# AnalogConnectors.net
KiCad netlist of a schematic drawn in Altium Designer
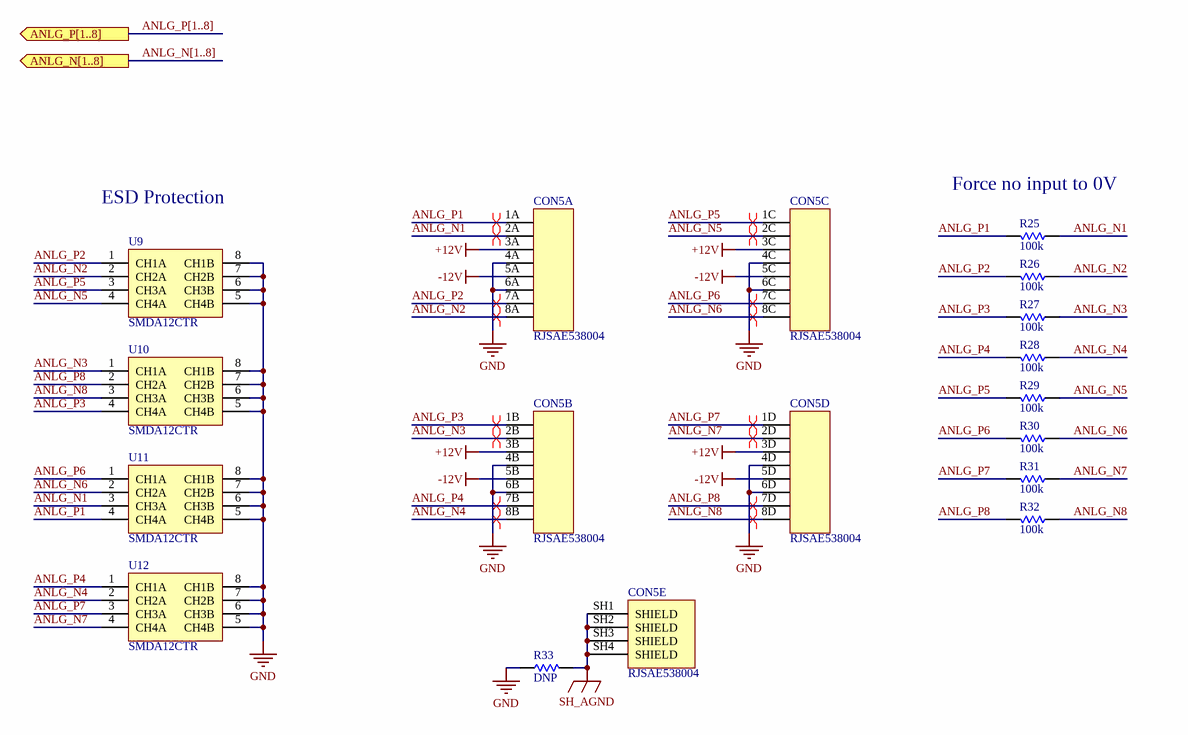
[diagram p0: AnalogConnectors.SchDoc]

(export (version "E")
  (design (tool "Eeschema 10.0.6"))
  (components
    (comp (ref "CON5")
      (value "RJSAE538004")
      (footprint "AMDC:RJSAE538004")
      (description "CONN MOD JACK 8P8C R/A SHIELDED")
      (libsource (lib "AMDC") (part "RJSAE538004"))
    )
    (comp (ref "R25")
      (value "100k")
      (footprint "AMDC:0603-RES")
      (description "Resistor")
      (libsource (lib "AMDC") (part "Resistor"))
    )
    (comp (ref "R26")
      (value "100k")
      (footprint "AMDC:0603-RES")
      (description "Resistor")
      (libsource (lib "AMDC") (part "Resistor"))
    )
    (comp (ref "R27")
      (value "100k")
      (footprint "AMDC:0603-RES")
      (description "Resistor")
      (libsource (lib "AMDC") (part "Resistor"))
    )
    (comp (ref "R28")
      (value "100k")
      (footprint "AMDC:0603-RES")
      (description "Resistor")
      (libsource (lib "AMDC") (part "Resistor"))
    )
    (comp (ref "R29")
      (value "100k")
      (footprint "AMDC:0603-RES")
      (description "Resistor")
      (libsource (lib "AMDC") (part "Resistor"))
    )
    (comp (ref "R30")
      (value "100k")
      (footprint "AMDC:0603-RES")
      (description "Resistor")
      (libsource (lib "AMDC") (part "Resistor"))
    )
    (comp (ref "R31")
      (value "100k")
      (footprint "AMDC:0603-RES")
      (description "Resistor")
      (libsource (lib "AMDC") (part "Resistor"))
    )
    (comp (ref "R32")
      (value "100k")
      (footprint "AMDC:0603-RES")
      (description "Resistor")
      (libsource (lib "AMDC") (part "Resistor"))
    )
    (comp (ref "R33")
      (value "DNP")
      (footprint "AMDC:0603-RES")
      (description "Resistor")
      (libsource (lib "AMDC") (part "Resistor"))
    )
    (comp (ref "U9")
      (value "SMDA12CTR")
      (footprint "AMDC:SOIC127P600X175-8N")
      (description "TVS DIODE 12V 19V 8SO")
      (libsource (lib "AMDC") (part "SMDA12CTR"))
    )
    (comp (ref "U10")
      (value "SMDA12CTR")
      (footprint "AMDC:SOIC127P600X175-8N")
      (description "TVS DIODE 12V 19V 8SO")
      (libsource (lib "AMDC") (part "SMDA12CTR"))
    )
    (comp (ref "U11")
      (value "SMDA12CTR")
      (footprint "AMDC:SOIC127P600X175-8N")
      (description "TVS DIODE 12V 19V 8SO")
      (libsource (lib "AMDC") (part "SMDA12CTR"))
    )
    (comp (ref "U12")
      (value "SMDA12CTR")
      (footprint "AMDC:SOIC127P600X175-8N")
      (description "TVS DIODE 12V 19V 8SO")
      (libsource (lib "AMDC") (part "SMDA12CTR"))
    )
  )
  (nets
    (net (code "1") (name "+12V") (class "Default")
      (node (ref "CON5") (pin "3A") (pinfunction "79_3A") (pintype "passive"))
      (node (ref "CON5") (pin "3B") (pinfunction "79_3B") (pintype "passive"))
      (node (ref "CON5") (pin "3C") (pinfunction "79_3C") (pintype "passive"))
      (node (ref "CON5") (pin "3D") (pinfunction "79_3D") (pintype "passive"))
    )
    (net (code "2") (name "-12V") (class "Default")
      (node (ref "CON5") (pin "5A") (pinfunction "79_5A") (pintype "passive"))
      (node (ref "CON5") (pin "5B") (pinfunction "79_5B") (pintype "passive"))
      (node (ref "CON5") (pin "5C") (pinfunction "79_5C") (pintype "passive"))
      (node (ref "CON5") (pin "5D") (pinfunction "79_5D") (pintype "passive"))
    )
    (net (code "3") (name "/ANLG_N1") (class "Default")
      (node (ref "CON5") (pin "2A") (pinfunction "79_2A") (pintype "passive"))
      (node (ref "R25") (pin "1") (pinfunction "1_1") (pintype "passive"))
      (node (ref "U11") (pin "3") (pinfunction "CH3A_3") (pintype "passive"))
    )
    (net (code "4") (name "/ANLG_N2") (class "Default")
      (node (ref "CON5") (pin "8A") (pinfunction "79_8A") (pintype "passive"))
      (node (ref "R26") (pin "1") (pinfunction "1_1") (pintype "passive"))
      (node (ref "U9") (pin "2") (pinfunction "CH2A_2") (pintype "passive"))
    )
    (net (code "5") (name "/ANLG_N3") (class "Default")
      (node (ref "CON5") (pin "2B") (pinfunction "79_2B") (pintype "passive"))
      (node (ref "R27") (pin "1") (pinfunction "1_1") (pintype "passive"))
      (node (ref "U10") (pin "1") (pinfunction "CH1A_1") (pintype "passive"))
    )
    (net (code "6") (name "/ANLG_N4") (class "Default")
      (node (ref "CON5") (pin "8B") (pinfunction "79_8B") (pintype "passive"))
      (node (ref "R28") (pin "1") (pinfunction "1_1") (pintype "passive"))
      (node (ref "U12") (pin "2") (pinfunction "CH2A_2") (pintype "passive"))
    )
    (net (code "7") (name "/ANLG_N5") (class "Default")
      (node (ref "CON5") (pin "2C") (pinfunction "79_2C") (pintype "passive"))
      (node (ref "R29") (pin "1") (pinfunction "1_1") (pintype "passive"))
      (node (ref "U9") (pin "4") (pinfunction "CH4A_4") (pintype "passive"))
    )
    (net (code "8") (name "/ANLG_N6") (class "Default")
      (node (ref "CON5") (pin "8C") (pinfunction "79_8C") (pintype "passive"))
      (node (ref "R30") (pin "1") (pinfunction "1_1") (pintype "passive"))
      (node (ref "U11") (pin "2") (pinfunction "CH2A_2") (pintype "passive"))
    )
    (net (code "9") (name "/ANLG_N7") (class "Default")
      (node (ref "CON5") (pin "2D") (pinfunction "79_2D") (pintype "passive"))
      (node (ref "R31") (pin "1") (pinfunction "1_1") (pintype "passive"))
      (node (ref "U12") (pin "4") (pinfunction "CH4A_4") (pintype "passive"))
    )
    (net (code "10") (name "/ANLG_N8") (class "Default")
      (node (ref "CON5") (pin "8D") (pinfunction "79_8D") (pintype "passive"))
      (node (ref "R32") (pin "1") (pinfunction "1_1") (pintype "passive"))
      (node (ref "U10") (pin "3") (pinfunction "CH3A_3") (pintype "passive"))
    )
    (net (code "12") (name "/ANLG_P1") (class "Default")
      (node (ref "CON5") (pin "1A") (pinfunction "79_1A") (pintype "passive"))
      (node (ref "R25") (pin "2") (pinfunction "2_2") (pintype "passive"))
      (node (ref "U11") (pin "4") (pinfunction "CH4A_4") (pintype "passive"))
    )
    (net (code "13") (name "/ANLG_P2") (class "Default")
      (node (ref "CON5") (pin "7A") (pinfunction "79_7A") (pintype "passive"))
      (node (ref "R26") (pin "2") (pinfunction "2_2") (pintype "passive"))
      (node (ref "U9") (pin "1") (pinfunction "CH1A_1") (pintype "passive"))
    )
    (net (code "14") (name "/ANLG_P3") (class "Default")
      (node (ref "CON5") (pin "1B") (pinfunction "79_1B") (pintype "passive"))
      (node (ref "R27") (pin "2") (pinfunction "2_2") (pintype "passive"))
      (node (ref "U10") (pin "4") (pinfunction "CH4A_4") (pintype "passive"))
    )
    (net (code "15") (name "/ANLG_P4") (class "Default")
      (node (ref "CON5") (pin "7B") (pinfunction "79_7B") (pintype "passive"))
      (node (ref "R28") (pin "2") (pinfunction "2_2") (pintype "passive"))
      (node (ref "U12") (pin "1") (pinfunction "CH1A_1") (pintype "passive"))
    )
    (net (code "16") (name "/ANLG_P5") (class "Default")
      (node (ref "CON5") (pin "1C") (pinfunction "79_1C") (pintype "passive"))
      (node (ref "R29") (pin "2") (pinfunction "2_2") (pintype "passive"))
      (node (ref "U9") (pin "3") (pinfunction "CH3A_3") (pintype "passive"))
    )
    (net (code "17") (name "/ANLG_P6") (class "Default")
      (node (ref "CON5") (pin "7C") (pinfunction "79_7C") (pintype "passive"))
      (node (ref "R30") (pin "2") (pinfunction "2_2") (pintype "passive"))
      (node (ref "U11") (pin "1") (pinfunction "CH1A_1") (pintype "passive"))
    )
    (net (code "18") (name "/ANLG_P7") (class "Default")
      (node (ref "CON5") (pin "1D") (pinfunction "79_1D") (pintype "passive"))
      (node (ref "R31") (pin "2") (pinfunction "2_2") (pintype "passive"))
      (node (ref "U12") (pin "3") (pinfunction "CH3A_3") (pintype "passive"))
    )
    (net (code "19") (name "/ANLG_P8") (class "Default")
      (node (ref "CON5") (pin "7D") (pinfunction "79_7D") (pintype "passive"))
      (node (ref "R32") (pin "2") (pinfunction "2_2") (pintype "passive"))
      (node (ref "U10") (pin "2") (pinfunction "CH2A_2") (pintype "passive"))
    )
    (net (code "21") (name "GND") (class "Default")
      (node (ref "CON5") (pin "4A") (pinfunction "79_4A") (pintype "passive"))
      (node (ref "CON5") (pin "4B") (pinfunction "79_4B") (pintype "passive"))
      (node (ref "CON5") (pin "4C") (pinfunction "79_4C") (pintype "passive"))
      (node (ref "CON5") (pin "4D") (pinfunction "79_4D") (pintype "passive"))
      (node (ref "CON5") (pin "6A") (pinfunction "79_6A") (pintype "passive"))
      (node (ref "CON5") (pin "6B") (pinfunction "79_6B") (pintype "passive"))
      (node (ref "CON5") (pin "6C") (pinfunction "79_6C") (pintype "passive"))
      (node (ref "CON5") (pin "6D") (pinfunction "79_6D") (pintype "passive"))
      (node (ref "R33") (pin "1") (pinfunction "1_1") (pintype "passive"))
      (node (ref "U10") (pin "5") (pinfunction "CH4B_5") (pintype "passive"))
      (node (ref "U10") (pin "6") (pinfunction "CH3B_6") (pintype "passive"))
      (node (ref "U10") (pin "7") (pinfunction "CH2B_7") (pintype "passive"))
      (node (ref "U10") (pin "8") (pinfunction "CH1B_8") (pintype "passive"))
      (node (ref "U11") (pin "5") (pinfunction "CH4B_5") (pintype "passive"))
      (node (ref "U11") (pin "6") (pinfunction "CH3B_6") (pintype "passive"))
      (node (ref "U11") (pin "7") (pinfunction "CH2B_7") (pintype "passive"))
      (node (ref "U11") (pin "8") (pinfunction "CH1B_8") (pintype "passive"))
      (node (ref "U12") (pin "5") (pinfunction "CH4B_5") (pintype "passive"))
      (node (ref "U12") (pin "6") (pinfunction "CH3B_6") (pintype "passive"))
      (node (ref "U12") (pin "7") (pinfunction "CH2B_7") (pintype "passive"))
      (node (ref "U12") (pin "8") (pinfunction "CH1B_8") (pintype "passive"))
      (node (ref "U9") (pin "5") (pinfunction "CH4B_5") (pintype "passive"))
      (node (ref "U9") (pin "6") (pinfunction "CH3B_6") (pintype "passive"))
      (node (ref "U9") (pin "7") (pinfunction "CH2B_7") (pintype "passive"))
      (node (ref "U9") (pin "8") (pinfunction "CH1B_8") (pintype "passive"))
    )
    (net (code "22") (name "SH_AGND") (class "Default")
      (node (ref "CON5") (pin "SH1") (pinfunction "SHIELD_SH1") (pintype "passive"))
      (node (ref "CON5") (pin "SH2") (pinfunction "SHIELD_SH2") (pintype "passive"))
      (node (ref "CON5") (pin "SH3") (pinfunction "SHIELD_SH3") (pintype "passive"))
      (node (ref "CON5") (pin "SH4") (pinfunction "SHIELD_SH4") (pintype "passive"))
      (node (ref "R33") (pin "2") (pinfunction "2_2") (pintype "passive"))
    )
  )
)
